# Digital_Port_L_Default_State_DIP.net
KiCad netlist of a schematic drawn in Altium Designer
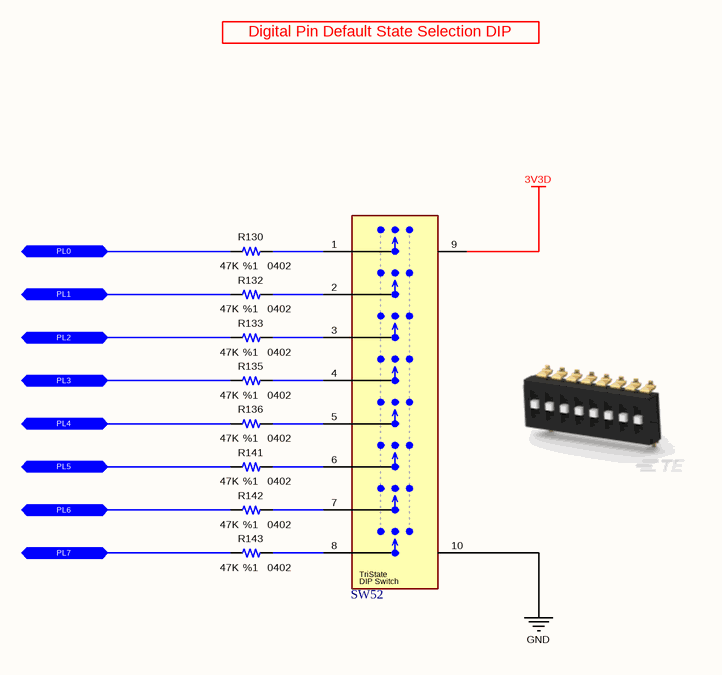
[diagram p0: Digital Port L Default State DIP.SchDoc]

(export (version "E")
  (design (tool "Eeschema 10.0.6"))
  (components
    (comp (ref "R130")
      (value "47K")
      (footprint "RESISTOR_0402")
      (description "Thick Film Resistors - SMD 1/16 W 47 Kohms 1%")
      (fields
        (field (name "MANUFACTURER PART NUMBER") "CRCW040247K0FKED")
        (field (name "MOUSER PART NUMBER") "71-CRCW0402-47K-E3")
        (field (name "TOLERANCE") "%1")
        (field (name "CASE") "0402")
      )
      (libsource (lib "Ovoo_Library") (part "Resistor - 47K"))
    )
    (comp (ref "R132")
      (value "47K")
      (footprint "RESISTOR_0402")
      (description "Thick Film Resistors - SMD 1/16 W 47 Kohms 1%")
      (fields
        (field (name "MANUFACTURER PART NUMBER") "CRCW040247K0FKED")
        (field (name "MOUSER PART NUMBER") "71-CRCW0402-47K-E3")
        (field (name "TOLERANCE") "%1")
        (field (name "CASE") "0402")
      )
      (libsource (lib "Ovoo_Library") (part "Resistor - 47K"))
    )
    (comp (ref "R133")
      (value "47K")
      (footprint "RESISTOR_0402")
      (description "Thick Film Resistors - SMD 1/16 W 47 Kohms 1%")
      (fields
        (field (name "MANUFACTURER PART NUMBER") "CRCW040247K0FKED")
        (field (name "MOUSER PART NUMBER") "71-CRCW0402-47K-E3")
        (field (name "TOLERANCE") "%1")
        (field (name "CASE") "0402")
      )
      (libsource (lib "Ovoo_Library") (part "Resistor - 47K"))
    )
    (comp (ref "R135")
      (value "47K")
      (footprint "RESISTOR_0402")
      (description "Thick Film Resistors - SMD 1/16 W 47 Kohms 1%")
      (fields
        (field (name "MANUFACTURER PART NUMBER") "CRCW040247K0FKED")
        (field (name "MOUSER PART NUMBER") "71-CRCW0402-47K-E3")
        (field (name "TOLERANCE") "%1")
        (field (name "CASE") "0402")
      )
      (libsource (lib "Ovoo_Library") (part "Resistor - 47K"))
    )
    (comp (ref "R136")
      (value "47K")
      (footprint "RESISTOR_0402")
      (description "Thick Film Resistors - SMD 1/16 W 47 Kohms 1%")
      (fields
        (field (name "MANUFACTURER PART NUMBER") "CRCW040247K0FKED")
        (field (name "MOUSER PART NUMBER") "71-CRCW0402-47K-E3")
        (field (name "TOLERANCE") "%1")
        (field (name "CASE") "0402")
      )
      (libsource (lib "Ovoo_Library") (part "Resistor - 47K"))
    )
    (comp (ref "R141")
      (value "47K")
      (footprint "RESISTOR_0402")
      (description "Thick Film Resistors - SMD 1/16 W 47 Kohms 1%")
      (fields
        (field (name "MANUFACTURER PART NUMBER") "CRCW040247K0FKED")
        (field (name "MOUSER PART NUMBER") "71-CRCW0402-47K-E3")
        (field (name "TOLERANCE") "%1")
        (field (name "CASE") "0402")
      )
      (libsource (lib "Ovoo_Library") (part "Resistor - 47K"))
    )
    (comp (ref "R142")
      (value "47K")
      (footprint "RESISTOR_0402")
      (description "Thick Film Resistors - SMD 1/16 W 47 Kohms 1%")
      (fields
        (field (name "MANUFACTURER PART NUMBER") "CRCW040247K0FKED")
        (field (name "MOUSER PART NUMBER") "71-CRCW0402-47K-E3")
        (field (name "TOLERANCE") "%1")
        (field (name "CASE") "0402")
      )
      (libsource (lib "Ovoo_Library") (part "Resistor - 47K"))
    )
    (comp (ref "R143")
      (value "47K")
      (footprint "RESISTOR_0402")
      (description "Thick Film Resistors - SMD 1/16 W 47 Kohms 1%")
      (fields
        (field (name "MANUFACTURER PART NUMBER") "CRCW040247K0FKED")
        (field (name "MOUSER PART NUMBER") "71-CRCW0402-47K-E3")
        (field (name "TOLERANCE") "%1")
        (field (name "CASE") "0402")
      )
      (libsource (lib "Ovoo_Library") (part "Resistor - 47K"))
    )
    (comp (ref "SW52")
      (value "DIP Switches/SIP Switches")
      (footprint "TDS08SGNNTR04")
      (description "DIP Switches/SIP Switches TRI-STATE DIP 8P G RAISED T&R")
      (fields
        (field (name "MANUFACTURER PART NUMBER") "TDS08SGNNTR04")
        (field (name "MOUSER PART NUMBER") "506-TDS08SGNNTR04")
      )
      (libsource (lib "Ovoo_Library") (part "Switch - DIP Switch (8 Pole TriState)"))
    )
  )
  (nets
    (net (code "1") (name "/PL0") (class "Default")
      (node (ref "R130") (pin "2") (pinfunction "2_2") (pintype "passive"))
    )
    (net (code "2") (name "/PL1") (class "Default")
      (node (ref "R132") (pin "2") (pinfunction "2_2") (pintype "passive"))
    )
    (net (code "3") (name "/PL2") (class "Default")
      (node (ref "R133") (pin "2") (pinfunction "2_2") (pintype "passive"))
    )
    (net (code "4") (name "/PL3") (class "Default")
      (node (ref "R135") (pin "2") (pinfunction "2_2") (pintype "passive"))
    )
    (net (code "5") (name "/PL4") (class "Default")
      (node (ref "R136") (pin "2") (pinfunction "2_2") (pintype "passive"))
    )
    (net (code "6") (name "/PL5") (class "Default")
      (node (ref "R141") (pin "2") (pinfunction "2_2") (pintype "passive"))
    )
    (net (code "7") (name "/PL6") (class "Default")
      (node (ref "R142") (pin "2") (pinfunction "2_2") (pintype "passive"))
    )
    (net (code "8") (name "/PL7") (class "Default")
      (node (ref "R143") (pin "2") (pinfunction "2_2") (pintype "passive"))
    )
    (net (code "9") (name "3V3D") (class "Default")
      (node (ref "SW52") (pin "9") (pinfunction "VCC_9") (pintype "passive"))
    )
    (net (code "10") (name "GND") (class "Default")
      (node (ref "SW52") (pin "10") (pinfunction "GND_10") (pintype "passive"))
    )
    (net (code "11") (name "Net-(R130-Pad1)") (class "Default")
      (node (ref "R130") (pin "1") (pinfunction "1_1") (pintype "passive"))
      (node (ref "SW52") (pin "1") (pinfunction "1_1") (pintype "passive"))
    )
    (net (code "12") (name "Net-(R132-Pad1)") (class "Default")
      (node (ref "R132") (pin "1") (pinfunction "1_1") (pintype "passive"))
      (node (ref "SW52") (pin "2") (pinfunction "2_2") (pintype "passive"))
    )
    (net (code "13") (name "Net-(R133-Pad1)") (class "Default")
      (node (ref "R133") (pin "1") (pinfunction "1_1") (pintype "passive"))
      (node (ref "SW52") (pin "3") (pinfunction "3_3") (pintype "passive"))
    )
    (net (code "14") (name "Net-(R135-Pad1)") (class "Default")
      (node (ref "R135") (pin "1") (pinfunction "1_1") (pintype "passive"))
      (node (ref "SW52") (pin "4") (pinfunction "4_4") (pintype "passive"))
    )
    (net (code "15") (name "Net-(R136-Pad1)") (class "Default")
      (node (ref "R136") (pin "1") (pinfunction "1_1") (pintype "passive"))
      (node (ref "SW52") (pin "5") (pinfunction "5_5") (pintype "passive"))
    )
    (net (code "16") (name "Net-(R141-Pad1)") (class "Default")
      (node (ref "R141") (pin "1") (pinfunction "1_1") (pintype "passive"))
      (node (ref "SW52") (pin "6") (pinfunction "6_6") (pintype "passive"))
    )
    (net (code "17") (name "Net-(R142-Pad1)") (class "Default")
      (node (ref "R142") (pin "1") (pinfunction "1_1") (pintype "passive"))
      (node (ref "SW52") (pin "7") (pinfunction "7_7") (pintype "passive"))
    )
    (net (code "18") (name "Net-(R143-Pad1)") (class "Default")
      (node (ref "R143") (pin "1") (pinfunction "1_1") (pintype "passive"))
      (node (ref "SW52") (pin "8") (pinfunction "8_8") (pintype "passive"))
    )
  )
)
